# Motor-Control-With-Password.net
KiCad netlist of a schematic drawn in EAGLE
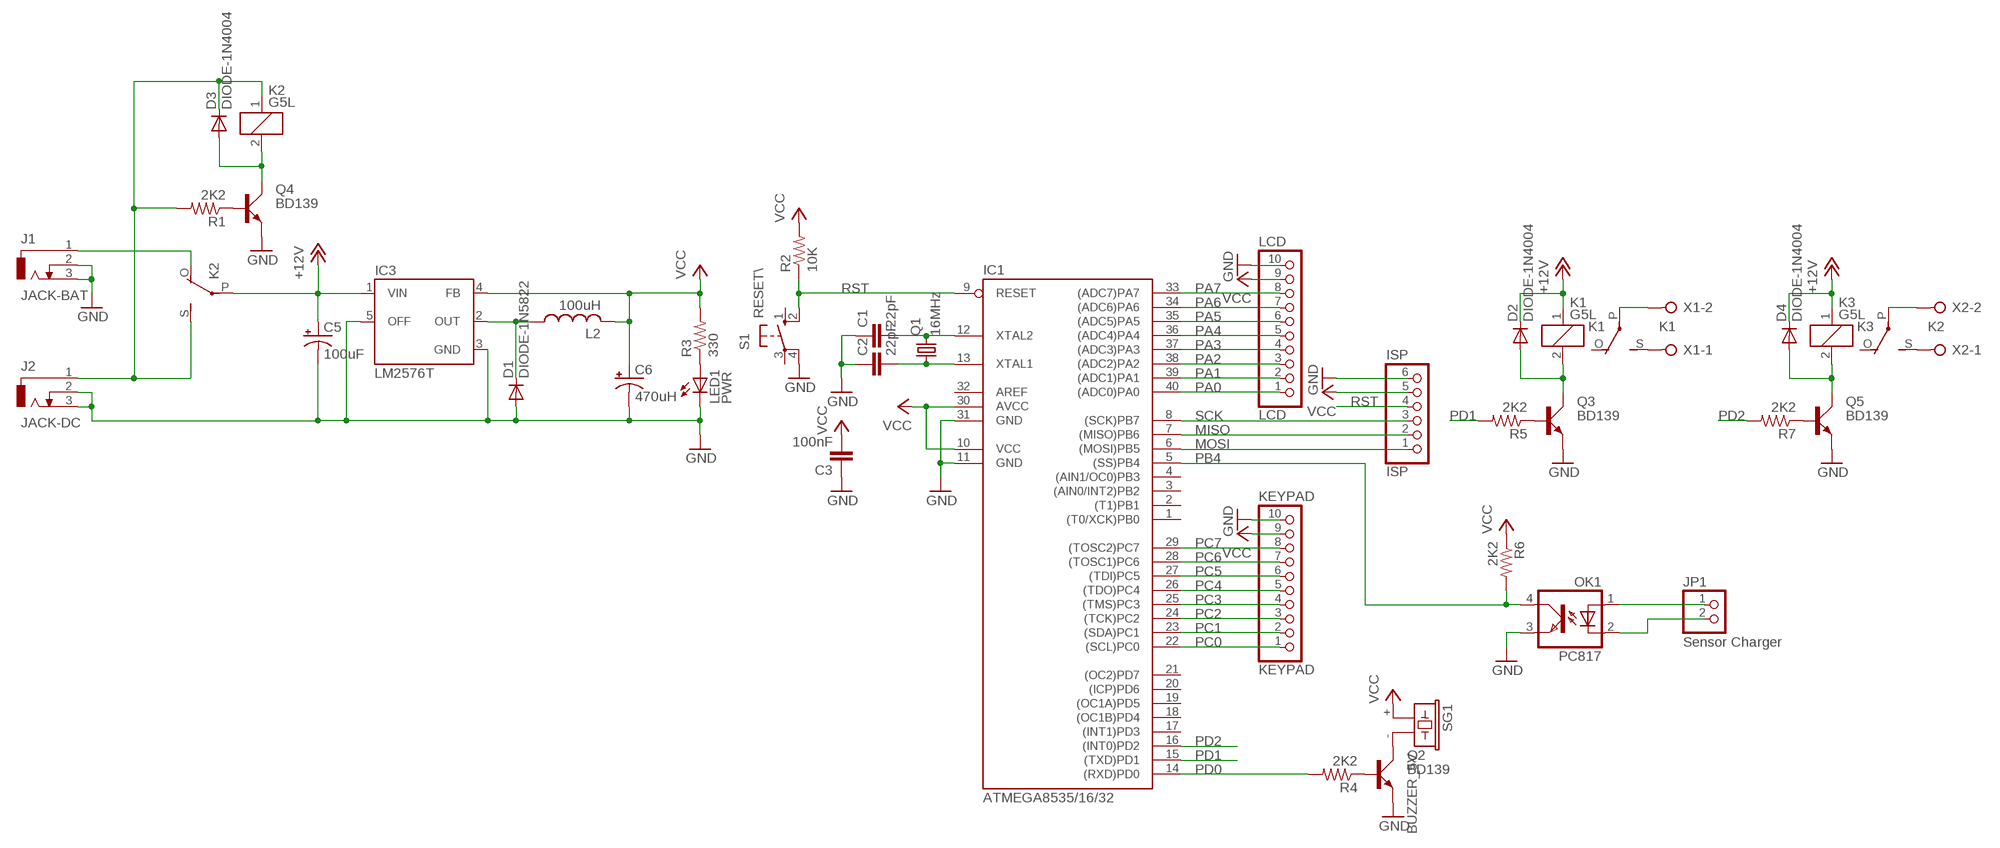
[diagram p0: schematic, sheet 1]

(export (version "E")
  (design (tool "Eeschema 10.0.6"))
  (components
    (comp (ref "C1")
      (value "22pF")
      (footprint "eagle-import:C025-024X044")
      (libsource (lib "eagle-import") (part "CAPACITOR-NONPOLAR025-024X044"))
    )
    (comp (ref "C2")
      (value "22pF")
      (footprint "eagle-import:C025-024X044")
      (libsource (lib "eagle-import") (part "CAPACITOR-NONPOLAR025-024X044"))
    )
    (comp (ref "C3")
      (value "100nF")
      (footprint "eagle-import:C025-024X044")
      (libsource (lib "eagle-import") (part "CAPACITOR-NONPOLAR025-024X044"))
    )
    (comp (ref "C5")
      (value "100uF")
      (footprint "eagle-import:E2,5-6")
      (libsource (lib "eagle-import") (part "CAPACITOR-POLARE2.5-6"))
    )
    (comp (ref "C6")
      (value "470uH")
      (footprint "eagle-import:E3,5-8")
      (libsource (lib "eagle-import") (part "CAPACITOR-POLARE3.5-8"))
    )
    (comp (ref "D1")
      (value "DIODE-1N5822")
      (footprint "eagle-import:DO201-15")
      (libsource (lib "eagle-import") (part "DIODE-1N5822"))
    )
    (comp (ref "D2")
      (value "DIODE-1N4004")
      (footprint "eagle-import:DO41-10")
      (libsource (lib "eagle-import") (part "DIODE-1N4004"))
    )
    (comp (ref "D3")
      (value "DIODE-1N4004")
      (footprint "eagle-import:DO41-10")
      (libsource (lib "eagle-import") (part "DIODE-1N4004"))
    )
    (comp (ref "D4")
      (value "DIODE-1N4004")
      (footprint "eagle-import:DO41-10")
      (libsource (lib "eagle-import") (part "DIODE-1N4004"))
    )
    (comp (ref "IC1")
      (value "ATMEGA8535/16/32")
      (footprint "eagle-import:DIL40")
      (fields (field (name "MPN") "ATMEGA32-16PU"))
      (libsource (lib "eagle-import") (part "ATMEGA8535/16/32"))
    )
    (comp (ref "IC3")
      (value "LM2576T")
      (footprint "eagle-import:TO220-5")
      (libsource (lib "eagle-import") (part "LM2576T"))
    )
    (comp (ref "ISP")
      (value "ISP")
      (footprint "eagle-import:1X06")
      (libsource (lib "eagle-import") (part "PINHD-1X6"))
    )
    (comp (ref "J1")
      (value "JACK-BAT")
      (footprint "eagle-import:DCJ0202")
      (libsource (lib "eagle-import") (part "JACK-DC"))
    )
    (comp (ref "J2")
      (value "JACK-DC")
      (footprint "eagle-import:DCJ0202")
      (libsource (lib "eagle-import") (part "JACK-DC"))
    )
    (comp (ref "JP1")
      (value "Sensor Charger")
      (footprint "eagle-import:1X02")
      (libsource (lib "eagle-import") (part "PINHD-1X2"))
    )
    (comp (ref "K1")
      (value "G5L")
      (footprint "eagle-import:G5LE")
      (libsource (lib "eagle-import") (part "G5L"))
    )
    (comp (ref "K2")
      (value "G5L")
      (footprint "eagle-import:G5LE")
      (libsource (lib "eagle-import") (part "G5L"))
    )
    (comp (ref "K3")
      (value "G5L")
      (footprint "eagle-import:G5LE")
      (libsource (lib "eagle-import") (part "G5L"))
    )
    (comp (ref "KEYPAD")
      (value "KEYPAD")
      (footprint "eagle-import:1X10")
      (libsource (lib "eagle-import") (part "PINHD-1X10"))
    )
    (comp (ref "L2")
      (value "100uH")
      (footprint "eagle-import:TJ3-U2")
      (libsource (lib "eagle-import") (part "INDUCTORTJ3-U2"))
    )
    (comp (ref "LCD")
      (value "LCD")
      (footprint "eagle-import:1X10")
      (libsource (lib "eagle-import") (part "PINHD-1X10"))
    )
    (comp (ref "LED1")
      (value "PWR")
      (footprint "eagle-import:LED3MM")
      (libsource (lib "eagle-import") (part "LED3MM"))
    )
    (comp (ref "OK1")
      (value "PC817")
      (footprint "eagle-import:DIL04")
      (fields (field (name "MPN") "PC817X4J000F"))
      (libsource (lib "eagle-import") (part "PC817"))
    )
    (comp (ref "Q1")
      (value "16MHz")
      (footprint "eagle-import:HC49_S")
      (libsource (lib "eagle-import") (part "CRYSTALHC49S"))
    )
    (comp (ref "Q2")
      (value "BD139")
      (footprint "eagle-import:TO126AV")
      (libsource (lib "eagle-import") (part "BD139"))
    )
    (comp (ref "Q3")
      (value "BD139")
      (footprint "eagle-import:TO126AV")
      (libsource (lib "eagle-import") (part "BD139"))
    )
    (comp (ref "Q4")
      (value "BD139")
      (footprint "eagle-import:TO126AV")
      (libsource (lib "eagle-import") (part "BD139"))
    )
    (comp (ref "Q5")
      (value "BD139")
      (footprint "eagle-import:TO126AV")
      (libsource (lib "eagle-import") (part "BD139"))
    )
    (comp (ref "R1")
      (value "2K2")
      (footprint "eagle-import:0207_10")
      (libsource (lib "eagle-import") (part "RESISTOR0207/10"))
    )
    (comp (ref "R2")
      (value "10K")
      (footprint "eagle-import:0207_10")
      (libsource (lib "eagle-import") (part "RESISTOR0207/10"))
    )
    (comp (ref "R3")
      (value "330")
      (footprint "eagle-import:0207_10")
      (libsource (lib "eagle-import") (part "RESISTOR0207/10"))
    )
    (comp (ref "R4")
      (value "2K2")
      (footprint "eagle-import:0207_10")
      (libsource (lib "eagle-import") (part "RESISTOR0207/10"))
    )
    (comp (ref "R5")
      (value "2K2")
      (footprint "eagle-import:0207_10")
      (libsource (lib "eagle-import") (part "RESISTOR0207/10"))
    )
    (comp (ref "R6")
      (value "2K2")
      (footprint "eagle-import:0207_10")
      (libsource (lib "eagle-import") (part "RESISTOR0207/10"))
    )
    (comp (ref "R7")
      (value "2K2")
      (footprint "eagle-import:0207_10")
      (libsource (lib "eagle-import") (part "RESISTOR0207/10"))
    )
    (comp (ref "S1")
      (value "RESET\\")
      (footprint "eagle-import:B3F-10XX")
      (fields (field (name "MPN") "B3F-1000"))
      (libsource (lib "eagle-import") (part "SW-PUSHBUTTON"))
    )
    (comp (ref "SG1")
      (value "BUZZER_5V")
      (footprint "eagle-import:BUZZER_F_CM12P")
      (libsource (lib "eagle-import") (part "BUZZER_5V"))
    )
    (comp (ref "X1")
      (value "K1")
      (footprint "eagle-import:W237-132")
      (libsource (lib "eagle-import") (part "W237-02P"))
    )
    (comp (ref "X2")
      (value "K2")
      (footprint "eagle-import:W237-132")
      (libsource (lib "eagle-import") (part "W237-02P"))
    )
  )
  (nets
    (net (code "1") (name "+12V") (class "Default")
      (node (ref "C5") (pin "+") (pinfunction "+_+") (pintype "passive"))
      (node (ref "D2") (pin "C") (pinfunction "C_C") (pintype "passive"))
      (node (ref "D4") (pin "C") (pinfunction "C_C") (pintype "passive"))
      (node (ref "IC3") (pin "1") (pinfunction "VIN_1") (pintype "power_in"))
      (node (ref "K1") (pin "1") (pinfunction "1_1") (pintype "passive"))
      (node (ref "K2") (pin "P") (pinfunction "P_P") (pintype "passive"))
      (node (ref "K3") (pin "1") (pinfunction "1_1") (pintype "passive"))
    )
    (net (code "2") (name "/MISO") (class "Default")
      (node (ref "IC1") (pin "7") (pinfunction "(MISO)PB6_7") (pintype "bidirectional"))
      (node (ref "ISP") (pin "2") (pinfunction "2_2") (pintype "passive"))
    )
    (net (code "3") (name "/MOSI") (class "Default")
      (node (ref "IC1") (pin "6") (pinfunction "(MOSI)PB5_6") (pintype "bidirectional"))
      (node (ref "ISP") (pin "1") (pinfunction "1_1") (pintype "passive"))
    )
    (net (code "4") (name "/PA0") (class "Default")
      (node (ref "IC1") (pin "40") (pinfunction "(ADC0)PA0_40") (pintype "bidirectional"))
      (node (ref "LCD") (pin "1") (pinfunction "1_1") (pintype "passive"))
    )
    (net (code "5") (name "/PA1") (class "Default")
      (node (ref "IC1") (pin "39") (pinfunction "(ADC1)PA1_39") (pintype "bidirectional"))
      (node (ref "LCD") (pin "2") (pinfunction "2_2") (pintype "passive"))
    )
    (net (code "6") (name "/PA2") (class "Default")
      (node (ref "IC1") (pin "38") (pinfunction "(ADC2)PA2_38") (pintype "bidirectional"))
      (node (ref "LCD") (pin "3") (pinfunction "3_3") (pintype "passive"))
    )
    (net (code "7") (name "/PA3") (class "Default")
      (node (ref "IC1") (pin "37") (pinfunction "(ADC3)PA3_37") (pintype "bidirectional"))
      (node (ref "LCD") (pin "4") (pinfunction "4_4") (pintype "passive"))
    )
    (net (code "8") (name "/PA4") (class "Default")
      (node (ref "IC1") (pin "36") (pinfunction "(ADC4)PA4_36") (pintype "bidirectional"))
      (node (ref "LCD") (pin "5") (pinfunction "5_5") (pintype "passive"))
    )
    (net (code "9") (name "/PA5") (class "Default")
      (node (ref "IC1") (pin "35") (pinfunction "(ADC5)PA5_35") (pintype "bidirectional"))
      (node (ref "LCD") (pin "6") (pinfunction "6_6") (pintype "passive"))
    )
    (net (code "10") (name "/PA6") (class "Default")
      (node (ref "IC1") (pin "34") (pinfunction "(ADC6)PA6_34") (pintype "bidirectional"))
      (node (ref "LCD") (pin "7") (pinfunction "7_7") (pintype "passive"))
    )
    (net (code "11") (name "/PA7") (class "Default")
      (node (ref "IC1") (pin "33") (pinfunction "(ADC7)PA7_33") (pintype "bidirectional"))
      (node (ref "LCD") (pin "8") (pinfunction "8_8") (pintype "passive"))
    )
    (net (code "12") (name "/PB4") (class "Default")
      (node (ref "IC1") (pin "5") (pinfunction "(SS)PB4_5") (pintype "bidirectional"))
      (node (ref "OK1") (pin "4") (pinfunction "COL_4") (pintype "passive"))
      (node (ref "R6") (pin "2") (pinfunction "2_2") (pintype "passive"))
    )
    (net (code "13") (name "/PC0") (class "Default")
      (node (ref "IC1") (pin "22") (pinfunction "(SCL)PC0_22") (pintype "bidirectional"))
      (node (ref "KEYPAD") (pin "1") (pinfunction "1_1") (pintype "passive"))
    )
    (net (code "14") (name "/PC1") (class "Default")
      (node (ref "IC1") (pin "23") (pinfunction "(SDA)PC1_23") (pintype "bidirectional"))
      (node (ref "KEYPAD") (pin "2") (pinfunction "2_2") (pintype "passive"))
    )
    (net (code "15") (name "/PC2") (class "Default")
      (node (ref "IC1") (pin "24") (pinfunction "(TCK)PC2_24") (pintype "bidirectional"))
      (node (ref "KEYPAD") (pin "3") (pinfunction "3_3") (pintype "passive"))
    )
    (net (code "16") (name "/PC3") (class "Default")
      (node (ref "IC1") (pin "25") (pinfunction "(TMS)PC3_25") (pintype "bidirectional"))
      (node (ref "KEYPAD") (pin "4") (pinfunction "4_4") (pintype "passive"))
    )
    (net (code "17") (name "/PC4") (class "Default")
      (node (ref "IC1") (pin "26") (pinfunction "(TDO)PC4_26") (pintype "bidirectional"))
      (node (ref "KEYPAD") (pin "5") (pinfunction "5_5") (pintype "passive"))
    )
    (net (code "18") (name "/PC5") (class "Default")
      (node (ref "IC1") (pin "27") (pinfunction "(TDI)PC5_27") (pintype "bidirectional"))
      (node (ref "KEYPAD") (pin "6") (pinfunction "6_6") (pintype "passive"))
    )
    (net (code "19") (name "/PC6") (class "Default")
      (node (ref "IC1") (pin "28") (pinfunction "(TOSC1)PC6_28") (pintype "bidirectional"))
      (node (ref "KEYPAD") (pin "7") (pinfunction "7_7") (pintype "passive"))
    )
    (net (code "20") (name "/PC7") (class "Default")
      (node (ref "IC1") (pin "29") (pinfunction "(TOSC2)PC7_29") (pintype "bidirectional"))
      (node (ref "KEYPAD") (pin "8") (pinfunction "8_8") (pintype "passive"))
    )
    (net (code "21") (name "/PD0") (class "Default")
      (node (ref "IC1") (pin "14") (pinfunction "(RXD)PD0_14") (pintype "bidirectional"))
      (node (ref "R4") (pin "2") (pinfunction "2_2") (pintype "passive"))
    )
    (net (code "22") (name "/PD1") (class "Default")
      (node (ref "IC1") (pin "15") (pinfunction "(TXD)PD1_15") (pintype "bidirectional"))
      (node (ref "R5") (pin "2") (pinfunction "2_2") (pintype "passive"))
    )
    (net (code "23") (name "/PD2") (class "Default")
      (node (ref "IC1") (pin "16") (pinfunction "(INT0)PD2_16") (pintype "bidirectional"))
      (node (ref "R7") (pin "2") (pinfunction "2_2") (pintype "passive"))
    )
    (net (code "24") (name "/RST") (class "Default")
      (node (ref "IC1") (pin "9") (pinfunction "RESET_9") (pintype "input"))
      (node (ref "ISP") (pin "4") (pinfunction "4_4") (pintype "passive"))
      (node (ref "R2") (pin "1") (pinfunction "1_1") (pintype "passive"))
      (node (ref "S1") (pin "2") (pinfunction "S1_2") (pintype "passive"))
    )
    (net (code "25") (name "/SCK") (class "Default")
      (node (ref "IC1") (pin "8") (pinfunction "(SCK)PB7_8") (pintype "bidirectional"))
      (node (ref "ISP") (pin "3") (pinfunction "3_3") (pintype "passive"))
    )
    (net (code "26") (name "GND") (class "Default")
      (node (ref "C1") (pin "1") (pinfunction "1_1") (pintype "passive"))
      (node (ref "C2") (pin "1") (pinfunction "1_1") (pintype "passive"))
      (node (ref "C3") (pin "1") (pinfunction "1_1") (pintype "passive"))
      (node (ref "C5") (pin "-") (pinfunction "-_-") (pintype "passive"))
      (node (ref "C6") (pin "-") (pinfunction "-_-") (pintype "passive"))
      (node (ref "D1") (pin "A") (pinfunction "A_A") (pintype "passive"))
      (node (ref "IC1") (pin "11") (pinfunction "GND_11") (pintype "power_in"))
      (node (ref "IC1") (pin "31") (pinfunction "GND_31") (pintype "power_in"))
      (node (ref "IC3") (pin "3") (pinfunction "GND_3") (pintype "power_in"))
      (node (ref "IC3") (pin "5") (pinfunction "OFF_5") (pintype "input"))
      (node (ref "ISP") (pin "6") (pinfunction "6_6") (pintype "passive"))
      (node (ref "J1") (pin "2") (pinfunction "2_2") (pintype "passive"))
      (node (ref "J1") (pin "3") (pinfunction "3_3") (pintype "passive"))
      (node (ref "J2") (pin "2") (pinfunction "2_2") (pintype "passive"))
      (node (ref "J2") (pin "3") (pinfunction "3_3") (pintype "passive"))
      (node (ref "KEYPAD") (pin "10") (pinfunction "10_10") (pintype "passive"))
      (node (ref "LCD") (pin "10") (pinfunction "10_10") (pintype "passive"))
      (node (ref "LED1") (pin "K") (pinfunction "C_K") (pintype "passive"))
      (node (ref "OK1") (pin "3") (pinfunction "EMIT_3") (pintype "passive"))
      (node (ref "Q2") (pin "E") (pinfunction "E_E") (pintype "passive"))
      (node (ref "Q3") (pin "E") (pinfunction "E_E") (pintype "passive"))
      (node (ref "Q4") (pin "E") (pinfunction "E_E") (pintype "passive"))
      (node (ref "Q5") (pin "E") (pinfunction "E_E") (pintype "passive"))
      (node (ref "S1") (pin "4") (pinfunction "P1_4") (pintype "passive"))
    )
    (net (code "27") (name "Net-(D2-PadA)") (class "Default")
      (node (ref "D2") (pin "A") (pinfunction "A_A") (pintype "passive"))
      (node (ref "K1") (pin "2") (pinfunction "2_2") (pintype "passive"))
      (node (ref "Q3") (pin "C") (pinfunction "C_C") (pintype "passive"))
    )
    (net (code "28") (name "Net-(D3-PadA)") (class "Default")
      (node (ref "D3") (pin "A") (pinfunction "A_A") (pintype "passive"))
      (node (ref "K2") (pin "2") (pinfunction "2_2") (pintype "passive"))
      (node (ref "Q4") (pin "C") (pinfunction "C_C") (pintype "passive"))
    )
    (net (code "29") (name "Net-(D3-PadC)") (class "Default")
      (node (ref "D3") (pin "C") (pinfunction "C_C") (pintype "passive"))
      (node (ref "J2") (pin "1") (pinfunction "1_1") (pintype "passive"))
      (node (ref "K2") (pin "1") (pinfunction "1_1") (pintype "passive"))
      (node (ref "K2") (pin "S") (pinfunction "S_S") (pintype "passive"))
      (node (ref "R1") (pin "2") (pinfunction "2_2") (pintype "passive"))
    )
    (net (code "30") (name "Net-(D4-PadA)") (class "Default")
      (node (ref "D4") (pin "A") (pinfunction "A_A") (pintype "passive"))
      (node (ref "K3") (pin "2") (pinfunction "2_2") (pintype "passive"))
      (node (ref "Q5") (pin "C") (pinfunction "C_C") (pintype "passive"))
    )
    (net (code "31") (name "Net-(IC1-XTAL1)") (class "Default")
      (node (ref "C2") (pin "2") (pinfunction "2_2") (pintype "passive"))
      (node (ref "IC1") (pin "13") (pinfunction "XTAL1_13") (pintype "bidirectional"))
      (node (ref "Q1") (pin "1") (pinfunction "1_1") (pintype "passive"))
    )
    (net (code "32") (name "Net-(IC1-XTAL2)") (class "Default")
      (node (ref "C1") (pin "2") (pinfunction "2_2") (pintype "passive"))
      (node (ref "IC1") (pin "12") (pinfunction "XTAL2_12") (pintype "bidirectional"))
      (node (ref "Q1") (pin "2") (pinfunction "2_2") (pintype "passive"))
    )
    (net (code "33") (name "Net-(IC3-OUT)") (class "Default")
      (node (ref "D1") (pin "C") (pinfunction "C_C") (pintype "passive"))
      (node (ref "IC3") (pin "2") (pinfunction "OUT_2") (pintype "output"))
      (node (ref "L2") (pin "1") (pinfunction "1_1") (pintype "passive"))
    )
    (net (code "34") (name "Net-(J1-Pad1)") (class "Default")
      (node (ref "J1") (pin "1") (pinfunction "1_1") (pintype "passive"))
      (node (ref "K2") (pin "O") (pinfunction "O_O") (pintype "passive"))
    )
    (net (code "35") (name "Net-(LED1-PadA)") (class "Default")
      (node (ref "LED1") (pin "A") (pinfunction "A_A") (pintype "passive"))
      (node (ref "R3") (pin "1") (pinfunction "1_1") (pintype "passive"))
    )
    (net (code "36") (name "Net-(OK1-A)") (class "Default")
      (node (ref "JP1") (pin "1") (pinfunction "1_1") (pintype "passive"))
      (node (ref "OK1") (pin "1") (pinfunction "A_1") (pintype "passive"))
    )
    (net (code "37") (name "Net-(OK1-C)") (class "Default")
      (node (ref "JP1") (pin "2") (pinfunction "2_2") (pintype "passive"))
      (node (ref "OK1") (pin "2") (pinfunction "C_2") (pintype "passive"))
    )
    (net (code "38") (name "Net-(Q2-PadB)") (class "Default")
      (node (ref "Q2") (pin "B") (pinfunction "B_B") (pintype "passive"))
      (node (ref "R4") (pin "1") (pinfunction "1_1") (pintype "passive"))
    )
    (net (code "39") (name "Net-(Q3-PadB)") (class "Default")
      (node (ref "Q3") (pin "B") (pinfunction "B_B") (pintype "passive"))
      (node (ref "R5") (pin "1") (pinfunction "1_1") (pintype "passive"))
    )
    (net (code "40") (name "Net-(Q4-PadB)") (class "Default")
      (node (ref "Q4") (pin "B") (pinfunction "B_B") (pintype "passive"))
      (node (ref "R1") (pin "1") (pinfunction "1_1") (pintype "passive"))
    )
    (net (code "41") (name "Net-(Q5-PadB)") (class "Default")
      (node (ref "Q5") (pin "B") (pinfunction "B_B") (pintype "passive"))
      (node (ref "R7") (pin "1") (pinfunction "1_1") (pintype "passive"))
    )
    (net (code "42") (name "Net-(SG1-2)") (class "Default")
      (node (ref "Q2") (pin "C") (pinfunction "C_C") (pintype "passive"))
      (node (ref "SG1") (pin "-") (pinfunction "2_-") (pintype "passive"))
    )
    (net (code "43") (name "Net-(X1A-KL)") (class "Default")
      (node (ref "K1") (pin "S") (pinfunction "S_S") (pintype "passive"))
      (node (ref "X1") (pin "1") (pinfunction "KL_1") (pintype "passive"))
    )
    (net (code "44") (name "Net-(X1B-KL)") (class "Default")
      (node (ref "K1") (pin "P") (pinfunction "P_P") (pintype "passive"))
      (node (ref "X1") (pin "2") (pinfunction "KL_2") (pintype "passive"))
    )
    (net (code "45") (name "Net-(X2A-KL)") (class "Default")
      (node (ref "K3") (pin "S") (pinfunction "S_S") (pintype "passive"))
      (node (ref "X2") (pin "1") (pinfunction "KL_1") (pintype "passive"))
    )
    (net (code "46") (name "Net-(X2B-KL)") (class "Default")
      (node (ref "K3") (pin "P") (pinfunction "P_P") (pintype "passive"))
      (node (ref "X2") (pin "2") (pinfunction "KL_2") (pintype "passive"))
    )
    (net (code "47") (name "VCC") (class "Default")
      (node (ref "C3") (pin "2") (pinfunction "2_2") (pintype "passive"))
      (node (ref "C6") (pin "+") (pinfunction "+_+") (pintype "passive"))
      (node (ref "IC1") (pin "10") (pinfunction "VCC_10") (pintype "power_in"))
      (node (ref "IC1") (pin "30") (pinfunction "AVCC_30") (pintype "power_in"))
      (node (ref "IC3") (pin "4") (pinfunction "FB_4") (pintype "input"))
      (node (ref "ISP") (pin "5") (pinfunction "5_5") (pintype "passive"))
      (node (ref "KEYPAD") (pin "9") (pinfunction "9_9") (pintype "passive"))
      (node (ref "L2") (pin "2") (pinfunction "2_2") (pintype "passive"))
      (node (ref "LCD") (pin "9") (pinfunction "9_9") (pintype "passive"))
      (node (ref "R2") (pin "2") (pinfunction "2_2") (pintype "passive"))
      (node (ref "R3") (pin "2") (pinfunction "2_2") (pintype "passive"))
      (node (ref "R6") (pin "1") (pinfunction "1_1") (pintype "passive"))
      (node (ref "SG1") (pin "+") (pinfunction "1_+") (pintype "passive"))
    )
    (net (code "48") (name "unconnected-(IC1-(AIN0{slash}INT2)PB2-Pad3)") (class "Default")
      (node (ref "IC1") (pin "3") (pinfunction "(AIN0/INT2)PB2_3") (pintype "bidirectional"))
    )
    (net (code "49") (name "unconnected-(IC1-(AIN1{slash}OC0)PB3-Pad4)") (class "Default")
      (node (ref "IC1") (pin "4") (pinfunction "(AIN1/OC0)PB3_4") (pintype "bidirectional"))
    )
    (net (code "50") (name "unconnected-(IC1-(ICP)PD6-Pad20)") (class "Default")
      (node (ref "IC1") (pin "20") (pinfunction "(ICP)PD6_20") (pintype "bidirectional"))
    )
    (net (code "51") (name "unconnected-(IC1-(INT1)PD3-Pad17)") (class "Default")
      (node (ref "IC1") (pin "17") (pinfunction "(INT1)PD3_17") (pintype "bidirectional"))
    )
    (net (code "52") (name "unconnected-(IC1-(OC1A)PD5-Pad19)") (class "Default")
      (node (ref "IC1") (pin "19") (pinfunction "(OC1A)PD5_19") (pintype "bidirectional"))
    )
    (net (code "53") (name "unconnected-(IC1-(OC1B)PD4-Pad18)") (class "Default")
      (node (ref "IC1") (pin "18") (pinfunction "(OC1B)PD4_18") (pintype "bidirectional"))
    )
    (net (code "54") (name "unconnected-(IC1-(OC2)PD7-Pad21)") (class "Default")
      (node (ref "IC1") (pin "21") (pinfunction "(OC2)PD7_21") (pintype "bidirectional"))
    )
    (net (code "55") (name "unconnected-(IC1-(T0{slash}XCK)PB0-Pad1)") (class "Default")
      (node (ref "IC1") (pin "1") (pinfunction "(T0/XCK)PB0_1") (pintype "bidirectional"))
    )
    (net (code "56") (name "unconnected-(IC1-(T1)PB1-Pad2)") (class "Default")
      (node (ref "IC1") (pin "2") (pinfunction "(T1)PB1_2") (pintype "bidirectional"))
    )
    (net (code "57") (name "unconnected-(IC1-AREF-Pad32)") (class "Default")
      (node (ref "IC1") (pin "32") (pinfunction "AREF_32") (pintype "passive"))
    )
    (net (code "58") (name "unconnected-(K1-PadO)") (class "Default")
      (node (ref "K1") (pin "O") (pinfunction "O_O") (pintype "passive"))
    )
    (net (code "59") (name "unconnected-(K3-PadO)") (class "Default")
      (node (ref "K3") (pin "O") (pinfunction "O_O") (pintype "passive"))
    )
    (net (code "60") (name "unconnected-(S1-P-Pad3)") (class "Default")
      (node (ref "S1") (pin "3") (pinfunction "P_3") (pintype "passive"))
    )
    (net (code "61") (name "unconnected-(S1-S-Pad1)") (class "Default")
      (node (ref "S1") (pin "1") (pinfunction "S_1") (pintype "passive"))
    )
  )
)
